# InteractivePlayPanel.net
KiCad netlist of a schematic drawn in EAGLE
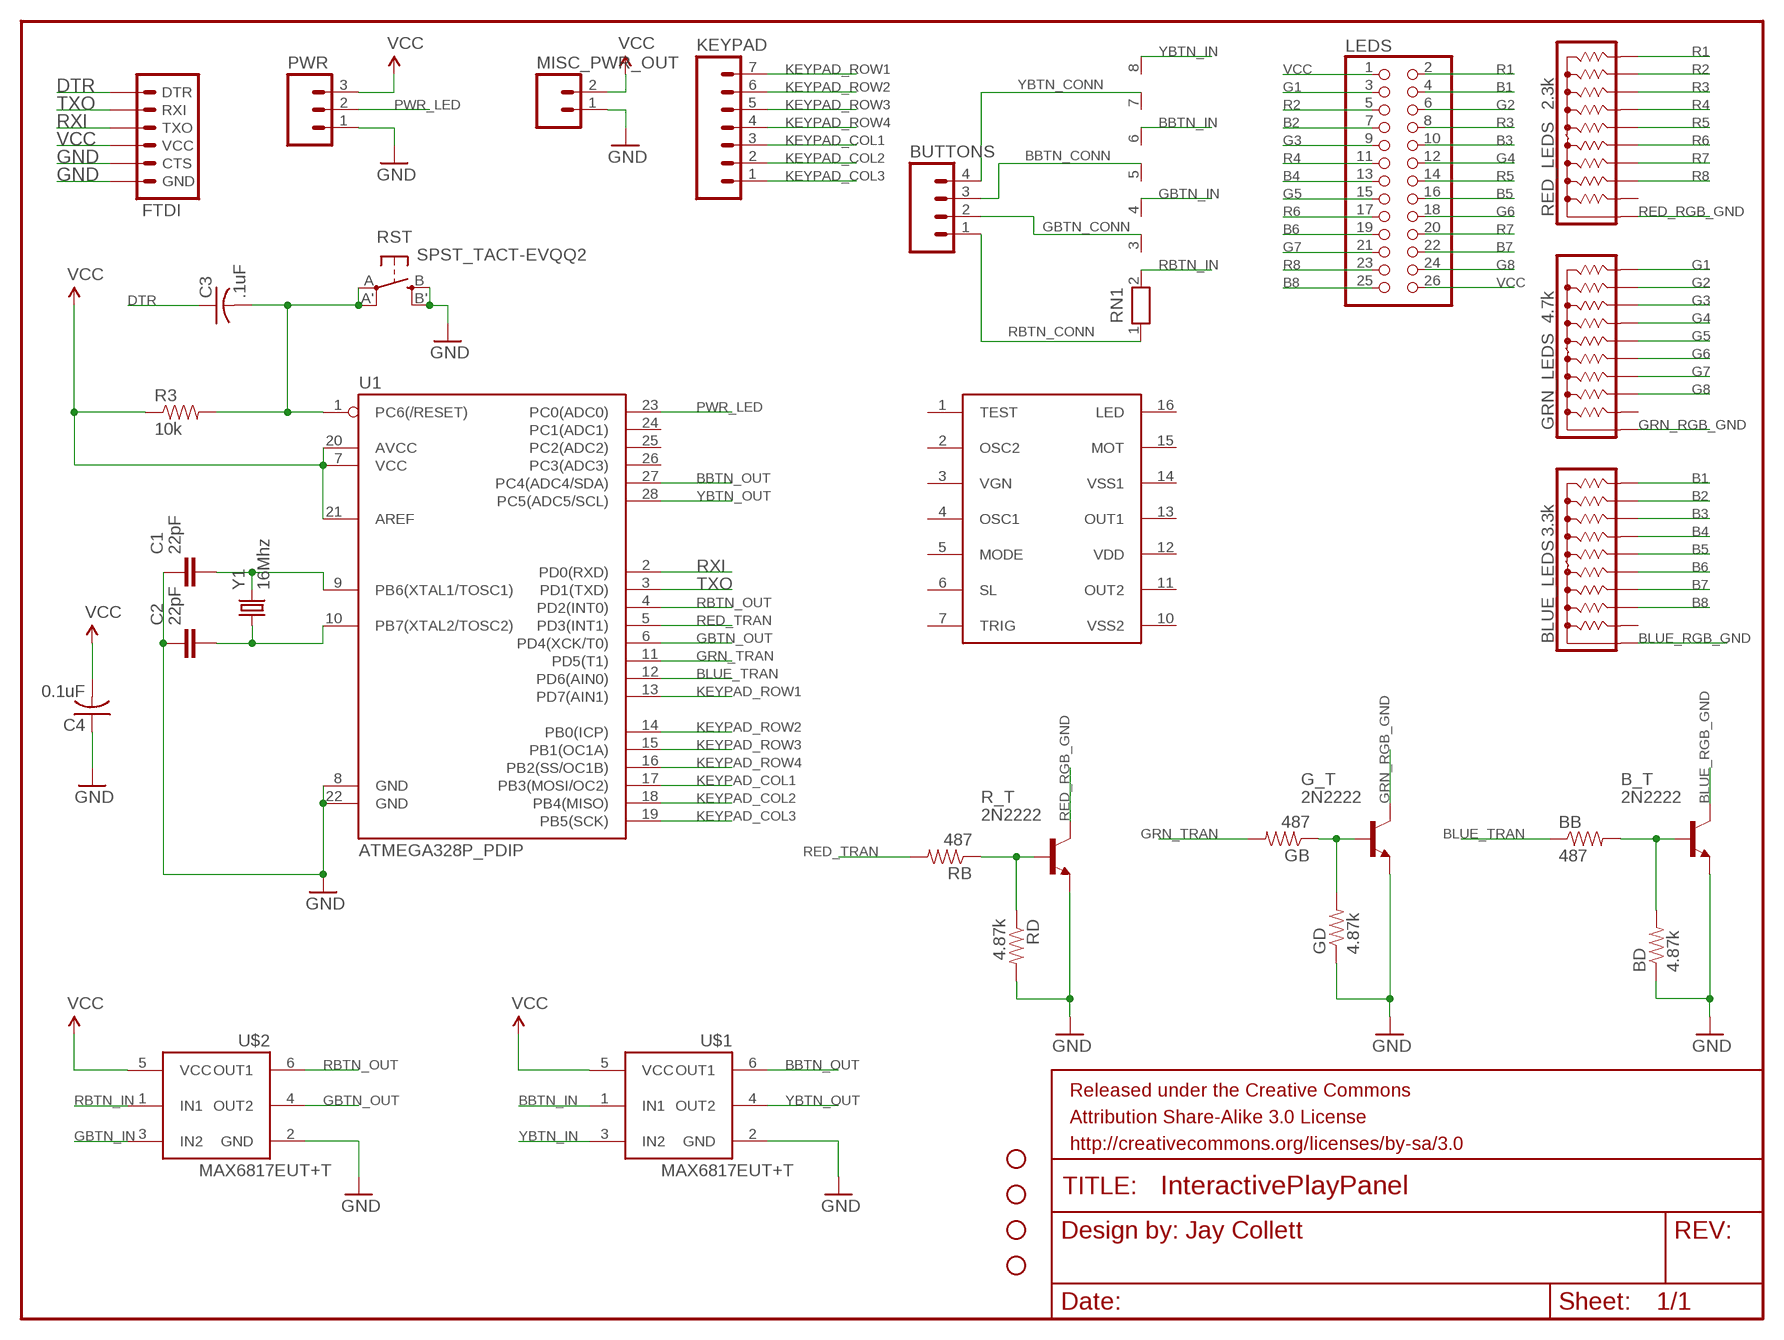
[diagram p0: schematic, sheet 1]

(export (version "E")
  (design (tool "Eeschema 10.0.6"))
  (components
    (comp (ref "BB")
      (value "487")
      (footprint "eagle-import:AXIAL-0.3EZ")
      (libsource (lib "eagle-import") (part "RESISTOREZ"))
    )
    (comp (ref "BD")
      (value "4.87k")
      (footprint "eagle-import:AXIAL-0.3EZ")
      (libsource (lib "eagle-import") (part "RESISTOREZ"))
    )
    (comp (ref "BLUE_LEDS")
      (value "3.3k")
      (footprint "eagle-import:SIP10")
      (libsource (lib "eagle-import") (part "4610X"))
    )
    (comp (ref "BUTTONS")
      (value "M04LOCK_LONGPADS")
      (footprint "eagle-import:1X04_LOCK_LONGPADS")
      (libsource (lib "eagle-import") (part "M04LOCK_LONGPADS"))
    )
    (comp (ref "B_T")
      (value "2N2222")
      (footprint "eagle-import:TO92-EBC-OVAL")
      (libsource (lib "eagle-import") (part "2N2222"))
    )
    (comp (ref "C1")
      (value "22pF")
      (footprint "eagle-import:C805")
      (libsource (lib "eagle-import") (part "CAPACITOR_NPOL-0805"))
    )
    (comp (ref "C2")
      (value "22pF")
      (footprint "eagle-import:C805")
      (libsource (lib "eagle-import") (part "CAPACITOR_NPOL-0805"))
    )
    (comp (ref "C3")
      (value ".1uF")
      (footprint "eagle-import:C0805")
      (libsource (lib "eagle-import") (part "C-USC0805"))
    )
    (comp (ref "C4")
      (value "0.1uF")
      (footprint "eagle-import:C0805")
      (libsource (lib "eagle-import") (part "C-USC0805"))
    )
    (comp (ref "FRAME1")
      (value "FRAME-LETTER")
      (footprint "eagle-import:CREATIVE_COMMONS")
      (libsource (lib "eagle-import") (part "FRAME-LETTER"))
    )
    (comp (ref "FTDI")
      (value "ARDUINO_SERIAL_PROGRAMLOCK")
      (footprint "eagle-import:1X06_LOCK")
      (libsource (lib "eagle-import") (part "ARDUINO_SERIAL_PROGRAMLOCK"))
    )
    (comp (ref "GB")
      (value "487")
      (footprint "eagle-import:AXIAL-0.3EZ")
      (libsource (lib "eagle-import") (part "RESISTOREZ"))
    )
    (comp (ref "GD")
      (value "4.87k")
      (footprint "eagle-import:AXIAL-0.3EZ")
      (libsource (lib "eagle-import") (part "RESISTOREZ"))
    )
    (comp (ref "GRN_LEDS")
      (value "4.7k")
      (footprint "eagle-import:SIP10")
      (libsource (lib "eagle-import") (part "4610X"))
    )
    (comp (ref "G_T")
      (value "2N2222")
      (footprint "eagle-import:TO92-EBC-OVAL")
      (libsource (lib "eagle-import") (part "2N2222"))
    )
    (comp (ref "KEYPAD")
      (value "M07LOCK_LONGPADS")
      (footprint "eagle-import:1X07_LOCK_LONGPADS")
      (libsource (lib "eagle-import") (part "M07LOCK_LONGPADS"))
    )
    (comp (ref "LEDS")
      (value "PINHD-2X13")
      (footprint "eagle-import:2X13")
      (libsource (lib "eagle-import") (part "PINHD-2X13"))
    )
    (comp (ref "MISC_PWR_OUT")
      (value "M02PTH3")
      (footprint "eagle-import:1X02_LONGPADS")
      (libsource (lib "eagle-import") (part "M02PTH3"))
    )
    (comp (ref "PWR")
      (value "M03LOCK_LONGPADS")
      (footprint "eagle-import:1X03_LOCK_LONGPADS")
      (libsource (lib "eagle-import") (part "M03LOCK_LONGPADS"))
    )
    (comp (ref "R3")
      (value "10k")
      (footprint "eagle-import:0805")
      (libsource (lib "eagle-import") (part "RESISTOR0805-RES"))
    )
    (comp (ref "RB")
      (value "487")
      (footprint "eagle-import:AXIAL-0.3EZ")
      (libsource (lib "eagle-import") (part "RESISTOREZ"))
    )
    (comp (ref "RD")
      (value "4.87k")
      (footprint "eagle-import:AXIAL-0.3EZ")
      (libsource (lib "eagle-import") (part "RESISTOREZ"))
    )
    (comp (ref "RED_LEDS")
      (value "2.3k")
      (footprint "eagle-import:SIP10")
      (libsource (lib "eagle-import") (part "4610X"))
    )
    (comp (ref "RN1")
      (value "RN07")
      (footprint "eagle-import:RN-8")
      (libsource (lib "eagle-import") (part "RN07"))
    )
    (comp (ref "RST")
      (value "SPST_TACT-EVQQ2")
      (footprint "eagle-import:EVQ-Q2")
      (libsource (lib "eagle-import") (part "SPST_TACT-EVQQ2"))
    )
    (comp (ref "R_T")
      (value "2N2222")
      (footprint "eagle-import:TO92-EBC-OVAL")
      (libsource (lib "eagle-import") (part "2N2222"))
    )
    (comp (ref "STANDOFF1")
      (value "STAND-OFF")
      (footprint "eagle-import:STAND-OFF")
      (libsource (lib "eagle-import") (part "STAND-OFF"))
    )
    (comp (ref "STANDOFF2")
      (value "STAND-OFF")
      (footprint "eagle-import:STAND-OFF")
      (libsource (lib "eagle-import") (part "STAND-OFF"))
    )
    (comp (ref "STANDOFF3")
      (value "STAND-OFF")
      (footprint "eagle-import:STAND-OFF")
      (libsource (lib "eagle-import") (part "STAND-OFF"))
    )
    (comp (ref "STANDOFF4")
      (value "STAND-OFF")
      (footprint "eagle-import:STAND-OFF")
      (libsource (lib "eagle-import") (part "STAND-OFF"))
    )
    (comp (ref "U$1")
      (value "MAX6817EUT+T")
      (footprint "eagle-import:SOT-23-6")
      (libsource (lib "eagle-import") (part "MAX6817EUT+T"))
    )
    (comp (ref "U$2")
      (value "MAX6817EUT+T")
      (footprint "eagle-import:SOT-23-6")
      (libsource (lib "eagle-import") (part "MAX6817EUT+T"))
    )
    (comp (ref "U$3")
      (value "HK326-X")
      (footprint "eagle-import:DIL16")
      (libsource (lib "eagle-import") (part "HK326-X"))
    )
    (comp (ref "U1")
      (value "ATMEGA328P_PDIP")
      (footprint "eagle-import:DIL28-3")
      (libsource (lib "eagle-import") (part "ATMEGA328P_PDIP"))
    )
    (comp (ref "Y1")
      (value "16Mhz")
      (footprint "eagle-import:CRYSTAL-SMD-5X3")
      (libsource (lib "eagle-import") (part "CRYSTAL5X3"))
    )
  )
  (nets
    (net (code "1") (name "/B1") (class "Default")
      (node (ref "BLUE_LEDS") (pin "10") (pinfunction "10_10") (pintype "passive"))
      (node (ref "LEDS") (pin "4") (pinfunction "4_4") (pintype "passive"))
    )
    (net (code "2") (name "/B2") (class "Default")
      (node (ref "BLUE_LEDS") (pin "9") (pinfunction "9_9") (pintype "passive"))
      (node (ref "LEDS") (pin "7") (pinfunction "7_7") (pintype "passive"))
    )
    (net (code "3") (name "/B3") (class "Default")
      (node (ref "BLUE_LEDS") (pin "8") (pinfunction "8_8") (pintype "passive"))
      (node (ref "LEDS") (pin "10") (pinfunction "10_10") (pintype "passive"))
    )
    (net (code "4") (name "/B4") (class "Default")
      (node (ref "BLUE_LEDS") (pin "7") (pinfunction "7_7") (pintype "passive"))
      (node (ref "LEDS") (pin "13") (pinfunction "13_13") (pintype "passive"))
    )
    (net (code "5") (name "/B5") (class "Default")
      (node (ref "BLUE_LEDS") (pin "6") (pinfunction "6_6") (pintype "passive"))
      (node (ref "LEDS") (pin "16") (pinfunction "16_16") (pintype "passive"))
    )
    (net (code "6") (name "/B6") (class "Default")
      (node (ref "BLUE_LEDS") (pin "5") (pinfunction "5_5") (pintype "passive"))
      (node (ref "LEDS") (pin "19") (pinfunction "19_19") (pintype "passive"))
    )
    (net (code "7") (name "/B7") (class "Default")
      (node (ref "BLUE_LEDS") (pin "4") (pinfunction "4_4") (pintype "passive"))
      (node (ref "LEDS") (pin "22") (pinfunction "22_22") (pintype "passive"))
    )
    (net (code "8") (name "/B8") (class "Default")
      (node (ref "BLUE_LEDS") (pin "3") (pinfunction "3_3") (pintype "passive"))
      (node (ref "LEDS") (pin "25") (pinfunction "25_25") (pintype "passive"))
    )
    (net (code "9") (name "/BBTN_CONN") (class "Default")
      (node (ref "BUTTONS") (pin "3") (pinfunction "3_3") (pintype "passive"))
      (node (ref "RN1") (pin "5") (pinfunction "5_5") (pintype "passive"))
    )
    (net (code "10") (name "/BBTN_IN") (class "Default")
      (node (ref "RN1") (pin "6") (pinfunction "6_6") (pintype "passive"))
      (node (ref "U$1") (pin "1") (pinfunction "IN1_1") (pintype "bidirectional"))
    )
    (net (code "11") (name "/BBTN_OUT") (class "Default")
      (node (ref "U$1") (pin "6") (pinfunction "OUT1_6") (pintype "bidirectional"))
      (node (ref "U1") (pin "27") (pinfunction "PC4(ADC4/SDA)_27") (pintype "bidirectional"))
    )
    (net (code "12") (name "/BLUE_RGB_GND") (class "Default")
      (node (ref "BLUE_LEDS") (pin "1") (pinfunction "1_1") (pintype "passive"))
      (node (ref "B_T") (pin "C") (pinfunction "C_C") (pintype "passive"))
    )
    (net (code "13") (name "/BLUE_TRAN") (class "Default")
      (node (ref "BB") (pin "P$1") (pinfunction "1_P$1") (pintype "passive"))
      (node (ref "U1") (pin "12") (pinfunction "PD6(AIN0)_12") (pintype "bidirectional"))
    )
    (net (code "14") (name "/DTR") (class "Default")
      (node (ref "C3") (pin "1") (pinfunction "1_1") (pintype "passive"))
      (node (ref "FTDI") (pin "1") (pinfunction "DTR_1") (pintype "passive"))
    )
    (net (code "15") (name "/G1") (class "Default")
      (node (ref "GRN_LEDS") (pin "10") (pinfunction "10_10") (pintype "passive"))
      (node (ref "LEDS") (pin "3") (pinfunction "3_3") (pintype "passive"))
    )
    (net (code "16") (name "/G2") (class "Default")
      (node (ref "GRN_LEDS") (pin "9") (pinfunction "9_9") (pintype "passive"))
      (node (ref "LEDS") (pin "6") (pinfunction "6_6") (pintype "passive"))
    )
    (net (code "17") (name "/G3") (class "Default")
      (node (ref "GRN_LEDS") (pin "8") (pinfunction "8_8") (pintype "passive"))
      (node (ref "LEDS") (pin "9") (pinfunction "9_9") (pintype "passive"))
    )
    (net (code "18") (name "/G4") (class "Default")
      (node (ref "GRN_LEDS") (pin "7") (pinfunction "7_7") (pintype "passive"))
      (node (ref "LEDS") (pin "12") (pinfunction "12_12") (pintype "passive"))
    )
    (net (code "19") (name "/G5") (class "Default")
      (node (ref "GRN_LEDS") (pin "6") (pinfunction "6_6") (pintype "passive"))
      (node (ref "LEDS") (pin "15") (pinfunction "15_15") (pintype "passive"))
    )
    (net (code "20") (name "/G6") (class "Default")
      (node (ref "GRN_LEDS") (pin "5") (pinfunction "5_5") (pintype "passive"))
      (node (ref "LEDS") (pin "18") (pinfunction "18_18") (pintype "passive"))
    )
    (net (code "21") (name "/G7") (class "Default")
      (node (ref "GRN_LEDS") (pin "4") (pinfunction "4_4") (pintype "passive"))
      (node (ref "LEDS") (pin "21") (pinfunction "21_21") (pintype "passive"))
    )
    (net (code "22") (name "/G8") (class "Default")
      (node (ref "GRN_LEDS") (pin "3") (pinfunction "3_3") (pintype "passive"))
      (node (ref "LEDS") (pin "24") (pinfunction "24_24") (pintype "passive"))
    )
    (net (code "23") (name "/GBTN_CONN") (class "Default")
      (node (ref "BUTTONS") (pin "2") (pinfunction "2_2") (pintype "passive"))
      (node (ref "RN1") (pin "3") (pinfunction "3_3") (pintype "passive"))
    )
    (net (code "24") (name "/GBTN_IN") (class "Default")
      (node (ref "RN1") (pin "4") (pinfunction "4_4") (pintype "passive"))
      (node (ref "U$2") (pin "3") (pinfunction "IN2_3") (pintype "bidirectional"))
    )
    (net (code "25") (name "/GBTN_OUT") (class "Default")
      (node (ref "U$2") (pin "4") (pinfunction "OUT2_4") (pintype "bidirectional"))
      (node (ref "U1") (pin "6") (pinfunction "PD4(XCK/T0)_6") (pintype "bidirectional"))
    )
    (net (code "26") (name "/GRN_RGB_GND") (class "Default")
      (node (ref "GRN_LEDS") (pin "1") (pinfunction "1_1") (pintype "passive"))
      (node (ref "G_T") (pin "C") (pinfunction "C_C") (pintype "passive"))
    )
    (net (code "27") (name "/GRN_TRAN") (class "Default")
      (node (ref "GB") (pin "P$2") (pinfunction "2_P$2") (pintype "passive"))
      (node (ref "U1") (pin "11") (pinfunction "PD5(T1)_11") (pintype "bidirectional"))
    )
    (net (code "28") (name "/KEYPAD_COL1") (class "Default")
      (node (ref "KEYPAD") (pin "3") (pinfunction "3_3") (pintype "passive"))
      (node (ref "U1") (pin "17") (pinfunction "PB3(MOSI/OC2)_17") (pintype "bidirectional"))
    )
    (net (code "29") (name "/KEYPAD_COL2") (class "Default")
      (node (ref "KEYPAD") (pin "2") (pinfunction "2_2") (pintype "passive"))
      (node (ref "U1") (pin "18") (pinfunction "PB4(MISO)_18") (pintype "bidirectional"))
    )
    (net (code "30") (name "/KEYPAD_COL3") (class "Default")
      (node (ref "KEYPAD") (pin "1") (pinfunction "1_1") (pintype "passive"))
      (node (ref "U1") (pin "19") (pinfunction "PB5(SCK)_19") (pintype "bidirectional"))
    )
    (net (code "31") (name "/KEYPAD_ROW1") (class "Default")
      (node (ref "KEYPAD") (pin "7") (pinfunction "7_7") (pintype "passive"))
      (node (ref "U1") (pin "13") (pinfunction "PD7(AIN1)_13") (pintype "bidirectional"))
    )
    (net (code "32") (name "/KEYPAD_ROW2") (class "Default")
      (node (ref "KEYPAD") (pin "6") (pinfunction "6_6") (pintype "passive"))
      (node (ref "U1") (pin "14") (pinfunction "PB0(ICP)_14") (pintype "bidirectional"))
    )
    (net (code "33") (name "/KEYPAD_ROW3") (class "Default")
      (node (ref "KEYPAD") (pin "5") (pinfunction "5_5") (pintype "passive"))
      (node (ref "U1") (pin "15") (pinfunction "PB1(OC1A)_15") (pintype "bidirectional"))
    )
    (net (code "34") (name "/KEYPAD_ROW4") (class "Default")
      (node (ref "KEYPAD") (pin "4") (pinfunction "4_4") (pintype "passive"))
      (node (ref "U1") (pin "16") (pinfunction "PB2(SS/OC1B)_16") (pintype "bidirectional"))
    )
    (net (code "35") (name "/PWR_LED") (class "Default")
      (node (ref "PWR") (pin "2") (pinfunction "2_2") (pintype "passive"))
      (node (ref "U1") (pin "23") (pinfunction "PC0(ADC0)_23") (pintype "bidirectional"))
    )
    (net (code "36") (name "/R1") (class "Default")
      (node (ref "LEDS") (pin "2") (pinfunction "2_2") (pintype "passive"))
      (node (ref "RED_LEDS") (pin "10") (pinfunction "10_10") (pintype "passive"))
    )
    (net (code "37") (name "/R2") (class "Default")
      (node (ref "LEDS") (pin "5") (pinfunction "5_5") (pintype "passive"))
      (node (ref "RED_LEDS") (pin "9") (pinfunction "9_9") (pintype "passive"))
    )
    (net (code "38") (name "/R3") (class "Default")
      (node (ref "LEDS") (pin "8") (pinfunction "8_8") (pintype "passive"))
      (node (ref "RED_LEDS") (pin "8") (pinfunction "8_8") (pintype "passive"))
    )
    (net (code "39") (name "/R4") (class "Default")
      (node (ref "LEDS") (pin "11") (pinfunction "11_11") (pintype "passive"))
      (node (ref "RED_LEDS") (pin "7") (pinfunction "7_7") (pintype "passive"))
    )
    (net (code "40") (name "/R5") (class "Default")
      (node (ref "LEDS") (pin "14") (pinfunction "14_14") (pintype "passive"))
      (node (ref "RED_LEDS") (pin "6") (pinfunction "6_6") (pintype "passive"))
    )
    (net (code "41") (name "/R6") (class "Default")
      (node (ref "LEDS") (pin "17") (pinfunction "17_17") (pintype "passive"))
      (node (ref "RED_LEDS") (pin "5") (pinfunction "5_5") (pintype "passive"))
    )
    (net (code "42") (name "/R7") (class "Default")
      (node (ref "LEDS") (pin "20") (pinfunction "20_20") (pintype "passive"))
      (node (ref "RED_LEDS") (pin "4") (pinfunction "4_4") (pintype "passive"))
    )
    (net (code "43") (name "/R8") (class "Default")
      (node (ref "LEDS") (pin "23") (pinfunction "23_23") (pintype "passive"))
      (node (ref "RED_LEDS") (pin "3") (pinfunction "3_3") (pintype "passive"))
    )
    (net (code "44") (name "/RBTN_CONN") (class "Default")
      (node (ref "BUTTONS") (pin "1") (pinfunction "1_1") (pintype "passive"))
      (node (ref "RN1") (pin "1") (pinfunction "1_1") (pintype "passive"))
    )
    (net (code "45") (name "/RBTN_IN") (class "Default")
      (node (ref "RN1") (pin "2") (pinfunction "2_2") (pintype "passive"))
      (node (ref "U$2") (pin "1") (pinfunction "IN1_1") (pintype "bidirectional"))
    )
    (net (code "46") (name "/RBTN_OUT") (class "Default")
      (node (ref "U$2") (pin "6") (pinfunction "OUT1_6") (pintype "bidirectional"))
      (node (ref "U1") (pin "4") (pinfunction "PD2(INT0)_4") (pintype "bidirectional"))
    )
    (net (code "47") (name "/RED_RGB_GND") (class "Default")
      (node (ref "RED_LEDS") (pin "1") (pinfunction "1_1") (pintype "passive"))
      (node (ref "R_T") (pin "C") (pinfunction "C_C") (pintype "passive"))
    )
    (net (code "48") (name "/RED_TRAN") (class "Default")
      (node (ref "RB") (pin "P$2") (pinfunction "2_P$2") (pintype "passive"))
      (node (ref "U1") (pin "5") (pinfunction "PD3(INT1)_5") (pintype "bidirectional"))
    )
    (net (code "49") (name "/RXI") (class "Default")
      (node (ref "FTDI") (pin "3") (pinfunction "TXO_3") (pintype "passive"))
      (node (ref "U1") (pin "2") (pinfunction "PD0(RXD)_2") (pintype "bidirectional"))
    )
    (net (code "50") (name "/TXO") (class "Default")
      (node (ref "FTDI") (pin "2") (pinfunction "RXI_2") (pintype "passive"))
      (node (ref "U1") (pin "3") (pinfunction "PD1(TXD)_3") (pintype "bidirectional"))
    )
    (net (code "51") (name "/YBTN_CONN") (class "Default")
      (node (ref "BUTTONS") (pin "4") (pinfunction "4_4") (pintype "passive"))
      (node (ref "RN1") (pin "7") (pinfunction "7_7") (pintype "passive"))
    )
    (net (code "52") (name "/YBTN_IN") (class "Default")
      (node (ref "RN1") (pin "8") (pinfunction "8_8") (pintype "passive"))
      (node (ref "U$1") (pin "3") (pinfunction "IN2_3") (pintype "bidirectional"))
    )
    (net (code "53") (name "/YBTN_OUT") (class "Default")
      (node (ref "U$1") (pin "4") (pinfunction "OUT2_4") (pintype "bidirectional"))
      (node (ref "U1") (pin "28") (pinfunction "PC5(ADC5/SCL)_28") (pintype "bidirectional"))
    )
    (net (code "54") (name "GND") (class "Default")
      (node (ref "BD") (pin "P$1") (pinfunction "1_P$1") (pintype "passive"))
      (node (ref "B_T") (pin "E") (pinfunction "E_E") (pintype "passive"))
      (node (ref "C1") (pin "1") (pinfunction "1_1") (pintype "passive"))
      (node (ref "C2") (pin "1") (pinfunction "1_1") (pintype "passive"))
      (node (ref "C4") (pin "1") (pinfunction "1_1") (pintype "passive"))
      (node (ref "FTDI") (pin "5") (pinfunction "CTS_5") (pintype "passive"))
      (node (ref "FTDI") (pin "6") (pinfunction "GND_6") (pintype "passive"))
      (node (ref "GD") (pin "P$1") (pinfunction "1_P$1") (pintype "passive"))
      (node (ref "G_T") (pin "E") (pinfunction "E_E") (pintype "passive"))
      (node (ref "MISC_PWR_OUT") (pin "1") (pinfunction "1_1") (pintype "passive"))
      (node (ref "PWR") (pin "1") (pinfunction "1_1") (pintype "passive"))
      (node (ref "RD") (pin "P$2") (pinfunction "2_P$2") (pintype "passive"))
      (node (ref "RST") (pin "B") (pinfunction "S_B") (pintype "passive"))
      (node (ref "RST") (pin "B'") (pinfunction "S1_B'") (pintype "passive"))
      (node (ref "R_T") (pin "E") (pinfunction "E_E") (pintype "passive"))
      (node (ref "U$1") (pin "2") (pinfunction "GND_2") (pintype "power_in"))
      (node (ref "U$2") (pin "2") (pinfunction "GND_2") (pintype "power_in"))
      (node (ref "U1") (pin "22") (pinfunction "GND_22") (pintype "bidirectional"))
      (node (ref "U1") (pin "8") (pinfunction "GND_8") (pintype "bidirectional"))
    )
    (net (code "55") (name "Net-(BB-2)") (class "Default")
      (node (ref "BB") (pin "P$2") (pinfunction "2_P$2") (pintype "passive"))
      (node (ref "BD") (pin "P$2") (pinfunction "2_P$2") (pintype "passive"))
      (node (ref "B_T") (pin "B") (pinfunction "B_B") (pintype "passive"))
    )
    (net (code "56") (name "Net-(GB-1)") (class "Default")
      (node (ref "GB") (pin "P$1") (pinfunction "1_P$1") (pintype "passive"))
      (node (ref "GD") (pin "P$2") (pinfunction "2_P$2") (pintype "passive"))
      (node (ref "G_T") (pin "B") (pinfunction "B_B") (pintype "passive"))
    )
    (net (code "57") (name "Net-(RB-1)") (class "Default")
      (node (ref "RB") (pin "P$1") (pinfunction "1_P$1") (pintype "passive"))
      (node (ref "RD") (pin "P$1") (pinfunction "1_P$1") (pintype "passive"))
      (node (ref "R_T") (pin "B") (pinfunction "B_B") (pintype "passive"))
    )
    (net (code "58") (name "Net-(RST-P)") (class "Default")
      (node (ref "C3") (pin "2") (pinfunction "2_2") (pintype "passive"))
      (node (ref "R3") (pin "2") (pinfunction "2_2") (pintype "passive"))
      (node (ref "RST") (pin "A") (pinfunction "P_A") (pintype "passive"))
      (node (ref "RST") (pin "A'") (pinfunction "P1_A'") (pintype "passive"))
      (node (ref "U1") (pin "1") (pinfunction "PC6(/RESET)_1") (pintype "bidirectional"))
    )
    (net (code "59") (name "Net-(U1-PB6(XTAL1{slash}TOSC1))") (class "Default")
      (node (ref "C1") (pin "2") (pinfunction "2_2") (pintype "passive"))
      (node (ref "U1") (pin "9") (pinfunction "PB6(XTAL1/TOSC1)_9") (pintype "bidirectional"))
      (node (ref "Y1") (pin "3") (pinfunction "2_3") (pintype "passive"))
    )
    (net (code "60") (name "Net-(U1-PB7(XTAL2{slash}TOSC2))") (class "Default")
      (node (ref "C2") (pin "2") (pinfunction "2_2") (pintype "passive"))
      (node (ref "U1") (pin "10") (pinfunction "PB7(XTAL2/TOSC2)_10") (pintype "bidirectional"))
      (node (ref "Y1") (pin "1") (pinfunction "1_1") (pintype "passive"))
    )
    (net (code "61") (name "VCC") (class "Default")
      (node (ref "C4") (pin "2") (pinfunction "2_2") (pintype "passive"))
      (node (ref "FTDI") (pin "4") (pinfunction "VCC_4") (pintype "passive"))
      (node (ref "LEDS") (pin "1") (pinfunction "1_1") (pintype "passive"))
      (node (ref "LEDS") (pin "26") (pinfunction "26_26") (pintype "passive"))
      (node (ref "MISC_PWR_OUT") (pin "2") (pinfunction "2_2") (pintype "passive"))
      (node (ref "PWR") (pin "3") (pinfunction "3_3") (pintype "passive"))
      (node (ref "R3") (pin "1") (pinfunction "1_1") (pintype "passive"))
      (node (ref "U$1") (pin "5") (pinfunction "VCC_5") (pintype "power_in"))
      (node (ref "U$2") (pin "5") (pinfunction "VCC_5") (pintype "power_in"))
      (node (ref "U1") (pin "20") (pinfunction "AVCC_20") (pintype "bidirectional"))
      (node (ref "U1") (pin "21") (pinfunction "AREF_21") (pintype "bidirectional"))
      (node (ref "U1") (pin "7") (pinfunction "VCC_7") (pintype "bidirectional"))
    )
    (net (code "62") (name "unconnected-(BLUE_LEDS-Pad2)") (class "Default")
      (node (ref "BLUE_LEDS") (pin "2") (pinfunction "2_2") (pintype "passive"))
    )
    (net (code "63") (name "unconnected-(GRN_LEDS-Pad2)") (class "Default")
      (node (ref "GRN_LEDS") (pin "2") (pinfunction "2_2") (pintype "passive"))
    )
    (net (code "64") (name "unconnected-(RED_LEDS-Pad2)") (class "Default")
      (node (ref "RED_LEDS") (pin "2") (pinfunction "2_2") (pintype "passive"))
    )
    (net (code "65") (name "unconnected-(U$3-LED-Pad16)") (class "Default")
      (node (ref "U$3") (pin "16") (pinfunction "LED_16") (pintype "bidirectional"))
    )
    (net (code "66") (name "unconnected-(U$3-MODE-Pad5)") (class "Default")
      (node (ref "U$3") (pin "5") (pinfunction "MODE_5") (pintype "bidirectional"))
    )
    (net (code "67") (name "unconnected-(U$3-MOT-Pad15)") (class "Default")
      (node (ref "U$3") (pin "15") (pinfunction "MOT_15") (pintype "bidirectional"))
    )
    (net (code "68") (name "unconnected-(U$3-OSC1-Pad4)") (class "Default")
      (node (ref "U$3") (pin "4") (pinfunction "OSC1_4") (pintype "bidirectional"))
    )
    (net (code "69") (name "unconnected-(U$3-OSC2-Pad2)") (class "Default")
      (node (ref "U$3") (pin "2") (pinfunction "OSC2_2") (pintype "bidirectional"))
    )
    (net (code "70") (name "unconnected-(U$3-OUT1-Pad13)") (class "Default")
      (node (ref "U$3") (pin "13") (pinfunction "OUT1_13") (pintype "bidirectional"))
    )
    (net (code "71") (name "unconnected-(U$3-OUT2-Pad11)") (class "Default")
      (node (ref "U$3") (pin "11") (pinfunction "OUT2_11") (pintype "bidirectional"))
    )
    (net (code "72") (name "unconnected-(U$3-SL-Pad6)") (class "Default")
      (node (ref "U$3") (pin "6") (pinfunction "SL_6") (pintype "bidirectional"))
    )
    (net (code "73") (name "unconnected-(U$3-TEST-Pad1)") (class "Default")
      (node (ref "U$3") (pin "1") (pinfunction "TEST_1") (pintype "bidirectional"))
    )
    (net (code "74") (name "unconnected-(U$3-TRIG-Pad7)") (class "Default")
      (node (ref "U$3") (pin "7") (pinfunction "TRIG_7") (pintype "bidirectional"))
    )
    (net (code "75") (name "unconnected-(U$3-VDD-Pad12)") (class "Default")
      (node (ref "U$3") (pin "12") (pinfunction "VDD_12") (pintype "bidirectional"))
    )
    (net (code "76") (name "unconnected-(U$3-VGN-Pad3)") (class "Default")
      (node (ref "U$3") (pin "3") (pinfunction "VGN_3") (pintype "bidirectional"))
    )
    (net (code "77") (name "unconnected-(U$3-VSS1-Pad14)") (class "Default")
      (node (ref "U$3") (pin "14") (pinfunction "VSS1_14") (pintype "bidirectional"))
    )
    (net (code "78") (name "unconnected-(U$3-VSS2-Pad10)") (class "Default")
      (node (ref "U$3") (pin "10") (pinfunction "VSS2_10") (pintype "bidirectional"))
    )
    (net (code "79") (name "unconnected-(U1-PC1(ADC1)-Pad24)") (class "Default")
      (node (ref "U1") (pin "24") (pinfunction "PC1(ADC1)_24") (pintype "bidirectional"))
    )
    (net (code "80") (name "unconnected-(U1-PC2(ADC2)-Pad25)") (class "Default")
      (node (ref "U1") (pin "25") (pinfunction "PC2(ADC2)_25") (pintype "bidirectional"))
    )
    (net (code "81") (name "unconnected-(U1-PC3(ADC3)-Pad26)") (class "Default")
      (node (ref "U1") (pin "26") (pinfunction "PC3(ADC3)_26") (pintype "bidirectional"))
    )
  )
)
